# 2_EVB-A32S1-M_MCU.net
KiCad netlist of a schematic drawn in Altium Designer
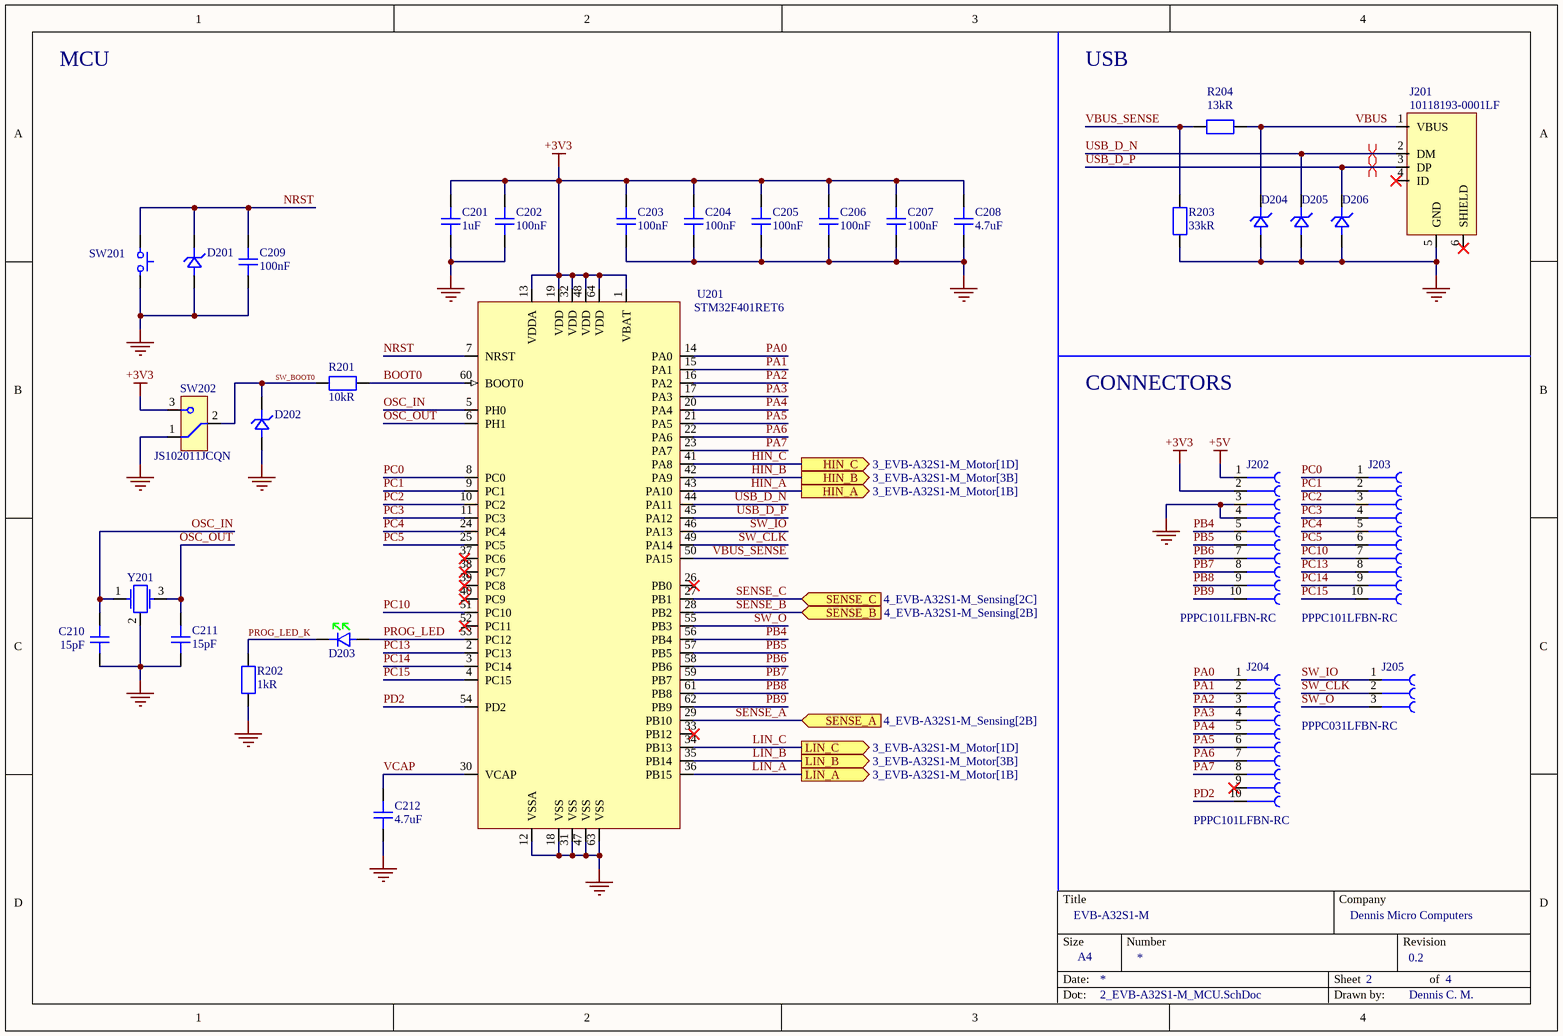
[diagram p0: 2_EVB-A32S1-M_MCU.SchDoc]

(export (version "E")
  (design (tool "Eeschema 10.0.6"))
  (components
    (comp (ref "C201")
      (value "1uF")
      (footprint "C_Yageo_CC_0603_A")
      (description "Multilayer Ceramic Capacitor, 1 uF, 16 V, ± 10%, X7R, 0603 [1608 Metric]")
      (fields (field (name "TOLERANCE") "10%") (field (name "VOLTAGE") "16V"))
      (libsource (lib "Dennis Micro Computers") (part "C"))
    )
    (comp (ref "C202")
      (value "100nF")
      (footprint "C_Samsung_CL_0402_A")
      (description "Multilayer Ceramic Capacitor, 0.1 uF, 10 V, ± 10%, X7R, 0402 [1005 Metric]")
      (fields (field (name "TOLERANCE") "10%") (field (name "Comment") "CL05B104KP5NNNC"))
      (libsource (lib "Dennis Micro Computers") (part "C"))
    )
    (comp (ref "C203")
      (value "100nF")
      (footprint "C_Samsung_CL_0402_A")
      (description "Multilayer Ceramic Capacitor, 0.1 uF, 10 V, ± 10%, X7R, 0402 [1005 Metric]")
      (fields (field (name "TOLERANCE") "10%") (field (name "Comment") "CL05B104KP5NNNC"))
      (libsource (lib "Dennis Micro Computers") (part "C"))
    )
    (comp (ref "C204")
      (value "100nF")
      (footprint "C_Samsung_CL_0402_A")
      (description "Multilayer Ceramic Capacitor, 0.1 uF, 10 V, ± 10%, X7R, 0402 [1005 Metric]")
      (fields (field (name "TOLERANCE") "10%") (field (name "Comment") "CL05B104KP5NNNC"))
      (libsource (lib "Dennis Micro Computers") (part "C"))
    )
    (comp (ref "C205")
      (value "100nF")
      (footprint "C_Samsung_CL_0402_A")
      (description "Multilayer Ceramic Capacitor, 0.1 uF, 10 V, ± 10%, X7R, 0402 [1005 Metric]")
      (fields (field (name "TOLERANCE") "10%") (field (name "Comment") "CL05B104KP5NNNC"))
      (libsource (lib "Dennis Micro Computers") (part "C"))
    )
    (comp (ref "C206")
      (value "100nF")
      (footprint "C_Samsung_CL_0402_A")
      (description "Multilayer Ceramic Capacitor, 0.1 uF, 10 V, ± 10%, X7R, 0402 [1005 Metric]")
      (fields (field (name "TOLERANCE") "10%") (field (name "Comment") "CL05B104KP5NNNC"))
      (libsource (lib "Dennis Micro Computers") (part "C"))
    )
    (comp (ref "C207")
      (value "100nF")
      (footprint "C_Samsung_CL_0402_A")
      (description "Multilayer Ceramic Capacitor, 0.1 uF, 10 V, ± 10%, X7R, 0402 [1005 Metric]")
      (fields (field (name "TOLERANCE") "10%") (field (name "Comment") "CL05B104KP5NNNC"))
      (libsource (lib "Dennis Micro Computers") (part "C"))
    )
    (comp (ref "C208")
      (value "4.7uF")
      (footprint "C_Samsung_CL_0402_A")
      (description "Multilayer Ceramic Capacitor, 4.7 uF, 10 V, ± 20%, X5R, 0402 [1005 Metric]")
      (fields (field (name "TOLERANCE") "20%") (field (name "Comment") "CL05A475MP5NRNC"))
      (libsource (lib "Dennis Micro Computers") (part "C"))
    )
    (comp (ref "C209")
      (value "100nF")
      (footprint "C_Samsung_CL_0402_A")
      (description "Multilayer Ceramic Capacitor, 0.1 uF, 10 V, ± 10%, X7R, 0402 [1005 Metric]")
      (fields (field (name "TOLERANCE") "10%") (field (name "Comment") "CL05B104KP5NNNC"))
      (libsource (lib "Dennis Micro Computers") (part "C"))
    )
    (comp (ref "C210")
      (value "15pF")
      (footprint "C_Yageo_CC_0402_A")
      (description "Multilayer Ceramic Capacitor, 15 pF, 10 V, ± 5%, X7R, 0402 [1005 Metric]")
      (fields (field (name "TOLERANCE") "5%") (field (name "VOLTAGE") "50V"))
      (libsource (lib "Dennis Micro Computers") (part "C"))
    )
    (comp (ref "C211")
      (value "15pF")
      (footprint "C_Yageo_CC_0402_A")
      (description "Multilayer Ceramic Capacitor, 15 pF, 10 V, ± 5%, X7R, 0402 [1005 Metric]")
      (fields (field (name "TOLERANCE") "5%") (field (name "VOLTAGE") "50V"))
      (libsource (lib "Dennis Micro Computers") (part "C"))
    )
    (comp (ref "C212")
      (value "4.7uF")
      (footprint "C_Samsung_CL_0402_A")
      (description "Multilayer Ceramic Capacitor, 4.7 uF, 10 V, ± 20%, X5R, 0402 [1005 Metric]")
      (fields (field (name "TOLERANCE") "20%") (field (name "Comment") "CL05A475MP5NRNC"))
      (libsource (lib "Dennis Micro Computers") (part "C"))
    )
    (comp (ref "D201")
      (value "D5V0F1U2S9-7")
      (footprint "D_TVS_Uni_Diodes_SOD-923_B")
      (description "Diode TVS Dual Uni-Dir 5.5V 250000W 2-Pin SOD-923 T/R")
      (libsource (lib "Dennis Micro Computers") (part "D_TVS_Uni"))
    )
    (comp (ref "D202")
      (value "D5V0F1U2S9-7")
      (footprint "D_TVS_Uni_Diodes_SOD-923_B")
      (description "Diode TVS Dual Uni-Dir 5.5V 250000W 2-Pin SOD-923 T/R")
      (libsource (lib "Dennis Micro Computers") (part "D_TVS_Uni"))
    )
    (comp (ref "D203")
      (value "LTST-C190GKT")
      (footprint "D_LED_Lite-On_Green_0603_A")
      (description "LED Uni-Color Green 565nm 2-Pin Chip LED T/R")
      (fields (field (name "VOLTAGE") "2V"))
      (libsource (lib "Dennis Micro Computers") (part "D_LED_Green"))
    )
    (comp (ref "D204")
      (value "D5V0F1U2S9-7")
      (footprint "D_TVS_Uni_Diodes_SOD-923_B")
      (description "Diode TVS Dual Uni-Dir 5.5V 250000W 2-Pin SOD-923 T/R")
      (libsource (lib "Dennis Micro Computers") (part "D_TVS_Uni"))
    )
    (comp (ref "D205")
      (value "D5V0F1U2S9-7")
      (footprint "D_TVS_Uni_Diodes_SOD-923_B")
      (description "Diode TVS Dual Uni-Dir 5.5V 250000W 2-Pin SOD-923 T/R")
      (libsource (lib "Dennis Micro Computers") (part "D_TVS_Uni"))
    )
    (comp (ref "D206")
      (value "D5V0F1U2S9-7")
      (footprint "D_TVS_Uni_Diodes_SOD-923_B")
      (description "Diode TVS Dual Uni-Dir 5.5V 250000W 2-Pin SOD-923 T/R")
      (libsource (lib "Dennis Micro Computers") (part "D_TVS_Uni"))
    )
    (comp (ref "J201")
      (value "10118193-0001LF")
      (footprint "J_USB_Micro-B_Amphenol_10118193-0001LF")
      (description "Usb Connector, 5 Contact(S), Female, Right Angle, Surface Mount Terminal, Locking, Receptacle")
      (libsource (lib "Dennis Micro Computers") (part "J_USB2_B_Micro"))
    )
    (comp (ref "J202")
      (value "PPPC101LFBN-RC")
      (footprint "J_Sullins_01x10_Socket_2.54mm")
      (description "10 Position Total Single Row 2.54 mm Pitch Straight Female Header")
      (libsource (lib "Dennis Micro Computers") (part "J_01x10_Socket"))
    )
    (comp (ref "J203")
      (value "PPPC101LFBN-RC")
      (footprint "J_Sullins_01x10_Socket_2.54mm")
      (description "10 Position Total Single Row 2.54 mm Pitch Straight Female Header")
      (libsource (lib "Dennis Micro Computers") (part "J_01x10_Socket"))
    )
    (comp (ref "J204")
      (value "PPPC101LFBN-RC")
      (footprint "J_Sullins_01x10_Socket_2.54mm")
      (description "10 Position Total Single Row 2.54 mm Pitch Straight Female Header")
      (libsource (lib "Dennis Micro Computers") (part "J_01x10_Socket"))
    )
    (comp (ref "J205")
      (value "PPPC031LFBN-RC")
      (footprint "J_Sullins_01x03_Socket_2.54mm")
      (description "3 Position Total Single Row 2.54 mm Pitch Straight Female Header")
      (libsource (lib "Dennis Micro Computers") (part "J_01x03_Socket"))
    )
    (comp (ref "R201")
      (value "10kR")
      (footprint "R_Yageo_RCL_0402_A")
      (description "SMD Chip Resistor, 10 kOhm, ± 1%, 62.5 mW, 0402 [1005 Metric], Thick Film, General Purpose")
      (fields (field (name "TOLERANCE") "1%") (field (name "Comment") "RC0402FR-0710KL"))
      (libsource (lib "Dennis Micro Computers") (part "R"))
    )
    (comp (ref "R202")
      (value "1kR")
      (footprint "R_Yageo_RCL_0402_A")
      (description "SMD Chip Resistor, 1 kOhm, ± 1%, 62.5 mW, 0402 [1005 Metric], Thick Film, General Purpose")
      (fields (field (name "TOLERANCE") "1%") (field (name "Comment") "RC0402FR-071KL"))
      (libsource (lib "Dennis Micro Computers") (part "R"))
    )
    (comp (ref "R203")
      (value "33kR")
      (footprint "R_Yageo_RCL_0402_A")
      (description "SMD Chip Resistor, 33 kOhm, ± 1%, 63 mW, 0402 [1005 Metric], Thick Film, General Purpose")
      (fields (field (name "TOLERANCE") "1%") (field (name "Comment") "RC0402FR-0733KL"))
      (libsource (lib "Dennis Micro Computers") (part "R"))
    )
    (comp (ref "R204")
      (value "13kR")
      (footprint "R_Yageo_RCL_0402_A")
      (description "SMD Chip Resistor, 13 kOhm, ± 1%, 63 mW, 0402 [1005 Metric], Thick Film, General Purpose")
      (fields (field (name "TOLERANCE") "1%") (field (name "Comment") "RC0402FR-0713KL"))
      (libsource (lib "Dennis Micro Computers") (part "R"))
    )
    (comp (ref "SW201")
      (value "PTS647SN50SMTR2LFS")
      (footprint "SW_Tactitle_SPST_C&K_PTS647SN50SMTR2LFS")
      (description "Switch Tactile N.O. SPST Round Button Gull Wing 0.05A 12VDC 100000Cycles 0.98N SMD T/R")
      (libsource (lib "Dennis Micro Computers") (part "SW_Tactile_SPST"))
    )
    (comp (ref "SW202")
      (value "JS102011JCQN")
      (footprint "SW_Slide_C&K_JS102011JCQN")
      (description "JS Series Sub-Miniature Slide Switch SPDT On-On Top Slide 0.3A 6VDC J-Lead Surface Mount T/R")
      (libsource (lib "Dennis Micro Computers") (part "SW_Slide_SPDT"))
    )
    (comp (ref "U201")
      (value "STM32F401RET6")
      (footprint "U_ST_LQFP64_B")
      (description "MCU 32-bit STM32 ARM Cortex M4 RISC 512KB Flash 1.8V/2.5V/3.3V 64-Pin LQFP Tray")
      (libsource (lib "Dennis Micro Computers") (part "U_STM32F401Rx"))
    )
    (comp (ref "Y201")
      (value "ECS-240-12-37B-CKY-TR")
      (footprint "Y_Crystal_GND24_ECS_240-12-37B-CKY-TR")
      (description "Crystal 24MHz ±10ppm (Tol) ±10ppm (Stability) 12pF FUND 50Ohm 4-Pin Mini-CSMD T/R")
      (libsource (lib "Dennis Micro Computers") (part "Y_Crystal_GND24"))
    )
  )
  (nets
    (net (code "1") (name "+3V3") (class "Default")
      (node (ref "C201") (pin "2") (pinfunction "2_2") (pintype "passive"))
      (node (ref "C202") (pin "2") (pinfunction "2_2") (pintype "passive"))
      (node (ref "C203") (pin "2") (pinfunction "2_2") (pintype "passive"))
      (node (ref "C204") (pin "2") (pinfunction "2_2") (pintype "passive"))
      (node (ref "C205") (pin "2") (pinfunction "2_2") (pintype "passive"))
      (node (ref "C206") (pin "2") (pinfunction "2_2") (pintype "passive"))
      (node (ref "C207") (pin "2") (pinfunction "2_2") (pintype "passive"))
      (node (ref "C208") (pin "2") (pinfunction "2_2") (pintype "passive"))
      (node (ref "J202") (pin "2") (pinfunction "2_2") (pintype "passive"))
      (node (ref "SW202") (pin "3") (pinfunction "3_3") (pintype "passive"))
      (node (ref "U201") (pin "1") (pinfunction "VBAT_1") (pintype "power_in"))
      (node (ref "U201") (pin "13") (pinfunction "VDDA_13") (pintype "power_in"))
      (node (ref "U201") (pin "19") (pinfunction "VDD_19") (pintype "power_in"))
      (node (ref "U201") (pin "32") (pinfunction "VDD_32") (pintype "power_in"))
      (node (ref "U201") (pin "48") (pinfunction "VDD_48") (pintype "power_in"))
      (node (ref "U201") (pin "64") (pinfunction "VDD_64") (pintype "power_in"))
    )
    (net (code "2") (name "+5V") (class "Default")
      (node (ref "J202") (pin "1") (pinfunction "1_1") (pintype "passive"))
    )
    (net (code "3") (name "/BOOT0") (class "Default")
      (node (ref "R201") (pin "2") (pinfunction "2_2") (pintype "passive"))
      (node (ref "U201") (pin "60") (pinfunction "BOOT0_60") (pintype "input"))
    )
    (net (code "4") (name "/HIN_A") (class "Default")
      (node (ref "U201") (pin "43") (pinfunction "PA10_43") (pintype "bidirectional"))
    )
    (net (code "5") (name "/HIN_B") (class "Default")
      (node (ref "U201") (pin "42") (pinfunction "PA9_42") (pintype "bidirectional"))
    )
    (net (code "6") (name "/HIN_C") (class "Default")
      (node (ref "U201") (pin "41") (pinfunction "PA8_41") (pintype "bidirectional"))
    )
    (net (code "7") (name "/LIN_A") (class "Default")
      (node (ref "U201") (pin "36") (pinfunction "PB15_36") (pintype "bidirectional"))
    )
    (net (code "8") (name "/LIN_B") (class "Default")
      (node (ref "U201") (pin "35") (pinfunction "PB14_35") (pintype "bidirectional"))
    )
    (net (code "9") (name "/LIN_C") (class "Default")
      (node (ref "U201") (pin "34") (pinfunction "PB13_34") (pintype "bidirectional"))
    )
    (net (code "10") (name "/NRST") (class "Default")
      (node (ref "C209") (pin "2") (pinfunction "2_2") (pintype "passive"))
      (node (ref "D201") (pin "1") (pinfunction "1_1") (pintype "passive"))
      (node (ref "SW201") (pin "1") (pinfunction "1_1") (pintype "passive"))
      (node (ref "U201") (pin "7") (pinfunction "NRST_7") (pintype "bidirectional"))
    )
    (net (code "11") (name "/OSC_IN") (class "Default")
      (node (ref "C210") (pin "2") (pinfunction "2_2") (pintype "passive"))
      (node (ref "U201") (pin "5") (pinfunction "PH0_5") (pintype "bidirectional"))
      (node (ref "Y201") (pin "1") (pinfunction "1_1") (pintype "passive"))
    )
    (net (code "12") (name "/OSC_OUT") (class "Default")
      (node (ref "C211") (pin "2") (pinfunction "2_2") (pintype "passive"))
      (node (ref "U201") (pin "6") (pinfunction "PH1_6") (pintype "bidirectional"))
      (node (ref "Y201") (pin "3") (pinfunction "3_3") (pintype "passive"))
    )
    (net (code "13") (name "/PA0") (class "Default")
      (node (ref "J204") (pin "1") (pinfunction "1_1") (pintype "passive"))
      (node (ref "U201") (pin "14") (pinfunction "PA0_14") (pintype "bidirectional"))
    )
    (net (code "14") (name "/PA1") (class "Default")
      (node (ref "J204") (pin "2") (pinfunction "2_2") (pintype "passive"))
      (node (ref "U201") (pin "15") (pinfunction "PA1_15") (pintype "bidirectional"))
    )
    (net (code "15") (name "/PA2") (class "Default")
      (node (ref "J204") (pin "3") (pinfunction "3_3") (pintype "passive"))
      (node (ref "U201") (pin "16") (pinfunction "PA2_16") (pintype "bidirectional"))
    )
    (net (code "16") (name "/PA3") (class "Default")
      (node (ref "J204") (pin "4") (pinfunction "4_4") (pintype "passive"))
      (node (ref "U201") (pin "17") (pinfunction "PA3_17") (pintype "bidirectional"))
    )
    (net (code "17") (name "/PA4") (class "Default")
      (node (ref "J204") (pin "5") (pinfunction "5_5") (pintype "passive"))
      (node (ref "U201") (pin "20") (pinfunction "PA4_20") (pintype "bidirectional"))
    )
    (net (code "18") (name "/PA5") (class "Default")
      (node (ref "J204") (pin "6") (pinfunction "6_6") (pintype "passive"))
      (node (ref "U201") (pin "21") (pinfunction "PA5_21") (pintype "bidirectional"))
    )
    (net (code "19") (name "/PA6") (class "Default")
      (node (ref "J204") (pin "7") (pinfunction "7_7") (pintype "passive"))
      (node (ref "U201") (pin "22") (pinfunction "PA6_22") (pintype "bidirectional"))
    )
    (net (code "20") (name "/PA7") (class "Default")
      (node (ref "J204") (pin "8") (pinfunction "8_8") (pintype "passive"))
      (node (ref "U201") (pin "23") (pinfunction "PA7_23") (pintype "bidirectional"))
    )
    (net (code "21") (name "/PB4") (class "Default")
      (node (ref "J202") (pin "5") (pinfunction "5_5") (pintype "passive"))
      (node (ref "U201") (pin "56") (pinfunction "PB4_56") (pintype "bidirectional"))
    )
    (net (code "22") (name "/PB5") (class "Default")
      (node (ref "J202") (pin "6") (pinfunction "6_6") (pintype "passive"))
      (node (ref "U201") (pin "57") (pinfunction "PB5_57") (pintype "bidirectional"))
    )
    (net (code "23") (name "/PB6") (class "Default")
      (node (ref "J202") (pin "7") (pinfunction "7_7") (pintype "passive"))
      (node (ref "U201") (pin "58") (pinfunction "PB6_58") (pintype "bidirectional"))
    )
    (net (code "24") (name "/PB7") (class "Default")
      (node (ref "J202") (pin "8") (pinfunction "8_8") (pintype "passive"))
      (node (ref "U201") (pin "59") (pinfunction "PB7_59") (pintype "bidirectional"))
    )
    (net (code "25") (name "/PB8") (class "Default")
      (node (ref "J202") (pin "9") (pinfunction "9_9") (pintype "passive"))
      (node (ref "U201") (pin "61") (pinfunction "PB8_61") (pintype "bidirectional"))
    )
    (net (code "26") (name "/PB9") (class "Default")
      (node (ref "J202") (pin "10") (pinfunction "10_10") (pintype "passive"))
      (node (ref "U201") (pin "62") (pinfunction "PB9_62") (pintype "bidirectional"))
    )
    (net (code "27") (name "/PC0") (class "Default")
      (node (ref "J203") (pin "1") (pinfunction "1_1") (pintype "passive"))
      (node (ref "U201") (pin "8") (pinfunction "PC0_8") (pintype "bidirectional"))
    )
    (net (code "28") (name "/PC1") (class "Default")
      (node (ref "J203") (pin "2") (pinfunction "2_2") (pintype "passive"))
      (node (ref "U201") (pin "9") (pinfunction "PC1_9") (pintype "bidirectional"))
    )
    (net (code "29") (name "/PC2") (class "Default")
      (node (ref "J203") (pin "3") (pinfunction "3_3") (pintype "passive"))
      (node (ref "U201") (pin "10") (pinfunction "PC2_10") (pintype "bidirectional"))
    )
    (net (code "30") (name "/PC3") (class "Default")
      (node (ref "J203") (pin "4") (pinfunction "4_4") (pintype "passive"))
      (node (ref "U201") (pin "11") (pinfunction "PC3_11") (pintype "bidirectional"))
    )
    (net (code "31") (name "/PC4") (class "Default")
      (node (ref "J203") (pin "5") (pinfunction "5_5") (pintype "passive"))
      (node (ref "U201") (pin "24") (pinfunction "PC4_24") (pintype "bidirectional"))
    )
    (net (code "32") (name "/PC5") (class "Default")
      (node (ref "J203") (pin "6") (pinfunction "6_6") (pintype "passive"))
      (node (ref "U201") (pin "25") (pinfunction "PC5_25") (pintype "bidirectional"))
    )
    (net (code "33") (name "/PC10") (class "Default")
      (node (ref "J203") (pin "7") (pinfunction "7_7") (pintype "passive"))
      (node (ref "U201") (pin "51") (pinfunction "PC10_51") (pintype "bidirectional"))
    )
    (net (code "34") (name "/PC13") (class "Default")
      (node (ref "J203") (pin "8") (pinfunction "8_8") (pintype "passive"))
      (node (ref "U201") (pin "2") (pinfunction "PC13_2") (pintype "bidirectional"))
    )
    (net (code "35") (name "/PC14") (class "Default")
      (node (ref "J203") (pin "9") (pinfunction "9_9") (pintype "passive"))
      (node (ref "U201") (pin "3") (pinfunction "PC14_3") (pintype "bidirectional"))
    )
    (net (code "36") (name "/PC15") (class "Default")
      (node (ref "J203") (pin "10") (pinfunction "10_10") (pintype "passive"))
      (node (ref "U201") (pin "4") (pinfunction "PC15_4") (pintype "bidirectional"))
    )
    (net (code "37") (name "/PD2") (class "Default")
      (node (ref "J204") (pin "10") (pinfunction "10_10") (pintype "passive"))
      (node (ref "U201") (pin "54") (pinfunction "PD2_54") (pintype "bidirectional"))
    )
    (net (code "38") (name "/PROG_LED") (class "Default")
      (node (ref "D203") (pin "2") (pinfunction "2_2") (pintype "passive"))
      (node (ref "U201") (pin "53") (pinfunction "PC12_53") (pintype "bidirectional"))
    )
    (net (code "39") (name "/PROG_LED_K") (class "Default")
      (node (ref "D203") (pin "1") (pinfunction "1_1") (pintype "passive"))
      (node (ref "R202") (pin "2") (pinfunction "2_2") (pintype "passive"))
    )
    (net (code "40") (name "/SENSE_A") (class "Default")
      (node (ref "U201") (pin "29") (pinfunction "PB10_29") (pintype "bidirectional"))
    )
    (net (code "41") (name "/SENSE_B") (class "Default")
      (node (ref "U201") (pin "28") (pinfunction "PB2_28") (pintype "bidirectional"))
    )
    (net (code "42") (name "/SENSE_C") (class "Default")
      (node (ref "U201") (pin "27") (pinfunction "PB1_27") (pintype "bidirectional"))
    )
    (net (code "43") (name "/SW_BOOT0") (class "Default")
      (node (ref "D202") (pin "1") (pinfunction "1_1") (pintype "passive"))
      (node (ref "R201") (pin "1") (pinfunction "1_1") (pintype "passive"))
      (node (ref "SW202") (pin "2") (pinfunction "2_2") (pintype "passive"))
    )
    (net (code "44") (name "/SW_CLK") (class "Default")
      (node (ref "J205") (pin "2") (pinfunction "2_2") (pintype "passive"))
      (node (ref "U201") (pin "49") (pinfunction "PA14_49") (pintype "bidirectional"))
    )
    (net (code "45") (name "/SW_IO") (class "Default")
      (node (ref "J205") (pin "1") (pinfunction "1_1") (pintype "passive"))
      (node (ref "U201") (pin "46") (pinfunction "PA13_46") (pintype "bidirectional"))
    )
    (net (code "46") (name "/SW_O") (class "Default")
      (node (ref "J205") (pin "3") (pinfunction "3_3") (pintype "passive"))
      (node (ref "U201") (pin "55") (pinfunction "PB3_55") (pintype "bidirectional"))
    )
    (net (code "47") (name "/USB_D_N") (class "Default")
      (node (ref "D205") (pin "1") (pinfunction "1_1") (pintype "passive"))
      (node (ref "J201") (pin "2") (pinfunction "DM_2") (pintype "bidirectional"))
      (node (ref "U201") (pin "44") (pinfunction "PA11_44") (pintype "bidirectional"))
    )
    (net (code "48") (name "/USB_D_P") (class "Default")
      (node (ref "D206") (pin "1") (pinfunction "1_1") (pintype "passive"))
      (node (ref "J201") (pin "3") (pinfunction "DP_3") (pintype "bidirectional"))
      (node (ref "U201") (pin "45") (pinfunction "PA12_45") (pintype "bidirectional"))
    )
    (net (code "49") (name "/VBUS") (class "Default")
      (node (ref "D204") (pin "1") (pinfunction "1_1") (pintype "passive"))
      (node (ref "J201") (pin "1") (pinfunction "VBUS_1") (pintype "power_in"))
      (node (ref "R204") (pin "2") (pinfunction "2_2") (pintype "passive"))
    )
    (net (code "50") (name "/VBUS_SENSE") (class "Default")
      (node (ref "R203") (pin "2") (pinfunction "2_2") (pintype "passive"))
      (node (ref "R204") (pin "1") (pinfunction "1_1") (pintype "passive"))
      (node (ref "U201") (pin "50") (pinfunction "PA15_50") (pintype "bidirectional"))
    )
    (net (code "51") (name "/VCAP") (class "Default")
      (node (ref "C212") (pin "2") (pinfunction "2_2") (pintype "passive"))
      (node (ref "U201") (pin "30") (pinfunction "VCAP_30") (pintype "power_in"))
    )
    (net (code "52") (name "GND") (class "Default")
      (node (ref "C201") (pin "1") (pinfunction "1_1") (pintype "passive"))
      (node (ref "C202") (pin "1") (pinfunction "1_1") (pintype "passive"))
      (node (ref "C203") (pin "1") (pinfunction "1_1") (pintype "passive"))
      (node (ref "C204") (pin "1") (pinfunction "1_1") (pintype "passive"))
      (node (ref "C205") (pin "1") (pinfunction "1_1") (pintype "passive"))
      (node (ref "C206") (pin "1") (pinfunction "1_1") (pintype "passive"))
      (node (ref "C207") (pin "1") (pinfunction "1_1") (pintype "passive"))
      (node (ref "C208") (pin "1") (pinfunction "1_1") (pintype "passive"))
      (node (ref "C209") (pin "1") (pinfunction "1_1") (pintype "passive"))
      (node (ref "C210") (pin "1") (pinfunction "1_1") (pintype "passive"))
      (node (ref "C211") (pin "1") (pinfunction "1_1") (pintype "passive"))
      (node (ref "C212") (pin "1") (pinfunction "1_1") (pintype "passive"))
      (node (ref "D201") (pin "2") (pinfunction "2_2") (pintype "passive"))
      (node (ref "D202") (pin "2") (pinfunction "2_2") (pintype "passive"))
      (node (ref "D204") (pin "2") (pinfunction "2_2") (pintype "passive"))
      (node (ref "D205") (pin "2") (pinfunction "2_2") (pintype "passive"))
      (node (ref "D206") (pin "2") (pinfunction "2_2") (pintype "passive"))
      (node (ref "J201") (pin "5") (pinfunction "GND_5") (pintype "power_in"))
      (node (ref "J202") (pin "3") (pinfunction "3_3") (pintype "passive"))
      (node (ref "J202") (pin "4") (pinfunction "4_4") (pintype "passive"))
      (node (ref "R202") (pin "1") (pinfunction "1_1") (pintype "passive"))
      (node (ref "R203") (pin "1") (pinfunction "1_1") (pintype "passive"))
      (node (ref "SW201") (pin "2") (pinfunction "2_2") (pintype "passive"))
      (node (ref "SW202") (pin "1") (pinfunction "1_1") (pintype "passive"))
      (node (ref "U201") (pin "12") (pinfunction "VSSA_12") (pintype "power_in"))
      (node (ref "U201") (pin "18") (pinfunction "VSS_18") (pintype "power_in"))
      (node (ref "U201") (pin "31") (pinfunction "VSS_31") (pintype "power_in"))
      (node (ref "U201") (pin "47") (pinfunction "VSS_47") (pintype "power_in"))
      (node (ref "U201") (pin "63") (pinfunction "VSS_63") (pintype "power_in"))
      (node (ref "Y201") (pin "2") (pinfunction "2_2") (pintype "passive"))
    )
    (net (code "53") (name "unconnected-(J201-ID-Pad4)") (class "Default")
      (node (ref "J201") (pin "4") (pinfunction "ID_4") (pintype "passive+no_connect"))
    )
    (net (code "54") (name "unconnected-(J201-SHIELD-Pad6)") (class "Default")
      (node (ref "J201") (pin "6") (pinfunction "SHIELD_6") (pintype "passive+no_connect"))
    )
    (net (code "55") (name "unconnected-(J204-Pad9)") (class "Default")
      (node (ref "J204") (pin "9") (pinfunction "9_9") (pintype "passive+no_connect"))
    )
    (net (code "56") (name "unconnected-(U201-PB0-Pad26)") (class "Default")
      (node (ref "U201") (pin "26") (pinfunction "PB0_26") (pintype "bidirectional+no_connect"))
    )
    (net (code "57") (name "unconnected-(U201-PB12-Pad33)") (class "Default")
      (node (ref "U201") (pin "33") (pinfunction "PB12_33") (pintype "bidirectional+no_connect"))
    )
    (net (code "58") (name "unconnected-(U201-PC6-Pad37)") (class "Default")
      (node (ref "U201") (pin "37") (pinfunction "PC6_37") (pintype "bidirectional+no_connect"))
    )
    (net (code "59") (name "unconnected-(U201-PC7-Pad38)") (class "Default")
      (node (ref "U201") (pin "38") (pinfunction "PC7_38") (pintype "bidirectional+no_connect"))
    )
    (net (code "60") (name "unconnected-(U201-PC8-Pad39)") (class "Default")
      (node (ref "U201") (pin "39") (pinfunction "PC8_39") (pintype "bidirectional+no_connect"))
    )
    (net (code "61") (name "unconnected-(U201-PC9-Pad40)") (class "Default")
      (node (ref "U201") (pin "40") (pinfunction "PC9_40") (pintype "bidirectional+no_connect"))
    )
    (net (code "62") (name "unconnected-(U201-PC11-Pad52)") (class "Default")
      (node (ref "U201") (pin "52") (pinfunction "PC11_52") (pintype "bidirectional+no_connect"))
    )
  )
)
